# Sheet1.net
KiCad netlist of a schematic drawn in Altium Designer
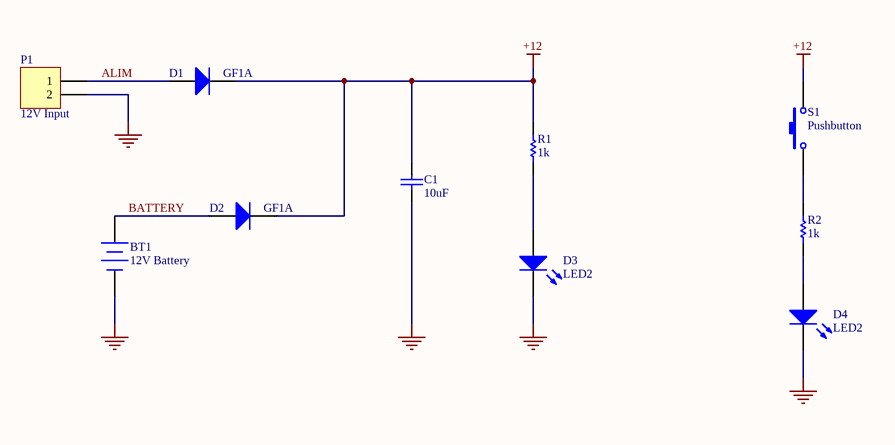
[diagram p0: Sheet1.SchDoc]

(export (version "E")
  (design (tool "Eeschema 10.0.6"))
  (components
    (comp (ref "BT1")
      (value "12V Battery")
      (footprint "BAT-2")
      (description "Multicell Battery")
      (fields (field (name "PUBLISHER") "Altium Limited"))
      (libsource (lib "Miscellaneous Devices") (part "Battery"))
    )
    (comp (ref "C1")
      (value "10uF")
      (footprint "RAD-0.3")
      (description "Capacitor")
      (fields (field (name "PUBLISHER") "Altium Limited"))
      (libsource (lib "Miscellaneous Devices") (part "Cap"))
    )
    (comp (ref "D1")
      (value "GF1A")
      (footprint "SMC")
      (description "Default Diode")
      (fields (field (name "PUBLISHER") "Altium Limited"))
      (libsource (lib "Miscellaneous Devices") (part "Diode"))
    )
    (comp (ref "D2")
      (value "GF1A")
      (footprint "SMC")
      (description "Default Diode")
      (fields (field (name "PUBLISHER") "Altium Limited"))
      (libsource (lib "Miscellaneous Devices") (part "Diode"))
    )
    (comp (ref "D3")
      (value "LED2")
      (footprint "LED-0")
      (description "Typical INFRARED GaAs LED")
      (fields (field (name "PUBLISHER") "Altium Limited"))
      (libsource (lib "Miscellaneous Devices") (part "LED0"))
    )
    (comp (ref "D4")
      (value "LED2")
      (footprint "LED-0")
      (description "Typical INFRARED GaAs LED")
      (fields (field (name "PUBLISHER") "Altium Limited"))
      (libsource (lib "Miscellaneous Devices") (part "LED0"))
    )
    (comp (ref "P1")
      (value "12V Input")
      (footprint "HDR1X2")
      (description "Header, 2-Pin")
      (fields (field (name "PUBLISHER") "Altium Limited"))
      (libsource (lib "Miscellaneous Connectors") (part "Header 2"))
    )
    (comp (ref "R1")
      (value "1k")
      (footprint "AXIAL-0.3")
      (description "Resistor")
      (fields (field (name "PUBLISHER") "Altium Limited"))
      (libsource (lib "Miscellaneous Devices") (part "Res1"))
    )
    (comp (ref "R2")
      (value "1k")
      (footprint "AXIAL-0.3")
      (description "Resistor")
      (fields (field (name "PUBLISHER") "Altium Limited"))
      (libsource (lib "Miscellaneous Devices") (part "Res1"))
    )
    (comp (ref "S1")
      (value "Pushbutton")
      (footprint "SPST-2")
      (description "Switch")
      (fields (field (name "PUBLISHER") "Altium Limited"))
      (libsource (lib "Miscellaneous Devices") (part "SW-PB"))
    )
  )
  (nets
    (net (code "1") (name "+12") (class "Default")
      (node (ref "C1") (pin "2") (pinfunction "2_2") (pintype "passive"))
      (node (ref "D1") (pin "2") (pinfunction "K_2") (pintype "passive"))
      (node (ref "D2") (pin "2") (pinfunction "K_2") (pintype "passive"))
      (node (ref "R1") (pin "2") (pinfunction "2_2") (pintype "passive"))
      (node (ref "S1") (pin "2") (pinfunction "2_2") (pintype "passive"))
    )
    (net (code "2") (name "/ALIM") (class "Default")
      (node (ref "D1") (pin "1") (pinfunction "A_1") (pintype "passive"))
      (node (ref "P1") (pin "1") (pinfunction "1_1") (pintype "passive"))
    )
    (net (code "3") (name "/BATTERY") (class "Default")
      (node (ref "BT1") (pin "1") (pinfunction "+_1") (pintype "passive"))
      (node (ref "D2") (pin "1") (pinfunction "A_1") (pintype "passive"))
    )
    (net (code "4") (name "GND") (class "Default")
      (node (ref "BT1") (pin "2") (pinfunction "-_2") (pintype "passive"))
      (node (ref "C1") (pin "1") (pinfunction "1_1") (pintype "passive"))
      (node (ref "D3") (pin "2") (pinfunction "K_2") (pintype "passive"))
      (node (ref "D4") (pin "2") (pinfunction "K_2") (pintype "passive"))
      (node (ref "P1") (pin "2") (pinfunction "2_2") (pintype "passive"))
    )
    (net (code "5") (name "Net-(D3-A)") (class "Default")
      (node (ref "D3") (pin "1") (pinfunction "A_1") (pintype "passive"))
      (node (ref "R1") (pin "1") (pinfunction "1_1") (pintype "passive"))
    )
    (net (code "6") (name "Net-(D4-A)") (class "Default")
      (node (ref "D4") (pin "1") (pinfunction "A_1") (pintype "passive"))
      (node (ref "R2") (pin "1") (pinfunction "1_1") (pintype "passive"))
    )
    (net (code "7") (name "Net-(R2-Pad2)") (class "Default")
      (node (ref "R2") (pin "2") (pinfunction "2_2") (pintype "passive"))
      (node (ref "S1") (pin "1") (pinfunction "1_1") (pintype "passive"))
    )
  )
)
